# bbf-supply.net
KiCad netlist of a schematic drawn in EAGLE
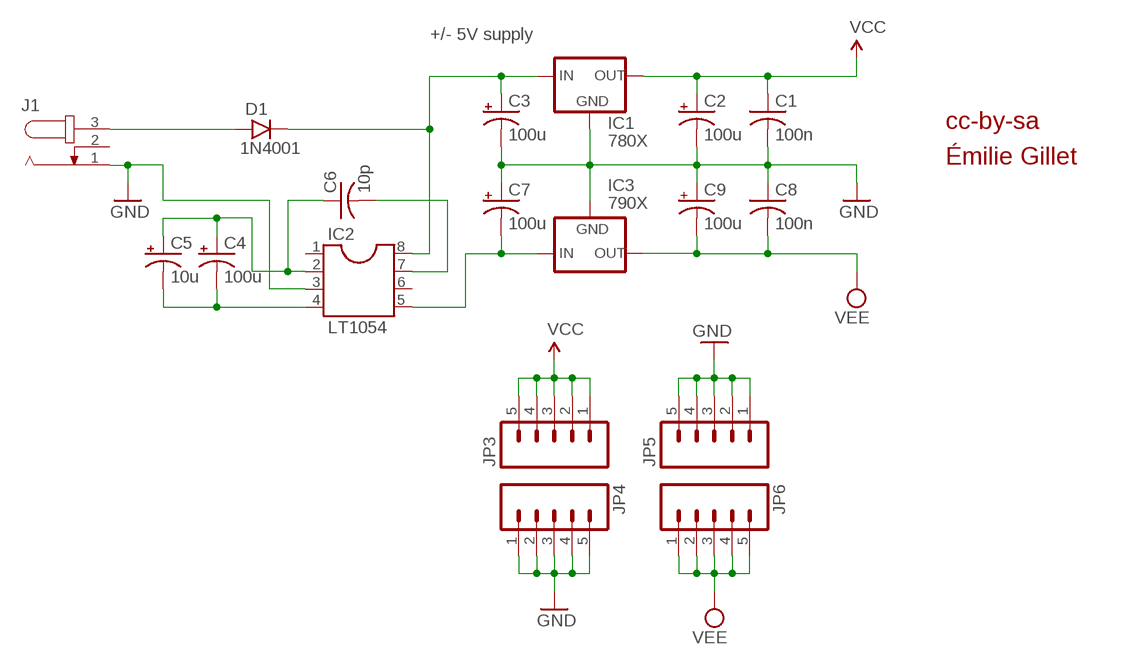
[diagram p0: schematic, sheet 1]

(export (version "E")
  (design (tool "Eeschema 10.0.6"))
  (components
    (comp (ref "C1")
      (value "100n")
      (footprint "eagle-import:C025-025X050")
      (libsource (lib "eagle-import") (part "C-US025-025X050"))
    )
    (comp (ref "C2")
      (value "100u")
      (footprint "eagle-import:E2,5-7")
      (libsource (lib "eagle-import") (part "CPOL-USE2.5-7"))
    )
    (comp (ref "C3")
      (value "100u")
      (footprint "eagle-import:E2,5-7")
      (libsource (lib "eagle-import") (part "CPOL-USE2.5-7"))
    )
    (comp (ref "C4")
      (value "100u")
      (footprint "eagle-import:E2,5-6")
      (libsource (lib "eagle-import") (part "CPOL-USE2.5-6"))
    )
    (comp (ref "C5")
      (value "10u")
      (footprint "eagle-import:E2,5-5")
      (libsource (lib "eagle-import") (part "CPOL-USE2.5-5"))
    )
    (comp (ref "C6")
      (value "10p")
      (footprint "eagle-import:C025-025X050")
      (libsource (lib "eagle-import") (part "C-US025-025X050"))
    )
    (comp (ref "C7")
      (value "100u")
      (footprint "eagle-import:E2,5-7")
      (libsource (lib "eagle-import") (part "CPOL-USE2.5-7"))
    )
    (comp (ref "C8")
      (value "100n")
      (footprint "eagle-import:C025-025X050")
      (libsource (lib "eagle-import") (part "C-US025-025X050"))
    )
    (comp (ref "C9")
      (value "100u")
      (footprint "eagle-import:E2,5-7")
      (libsource (lib "eagle-import") (part "CPOL-USE2.5-7"))
    )
    (comp (ref "D1")
      (value "1N4001")
      (footprint "eagle-import:DO41-3")
      (libsource (lib "eagle-import") (part "1N400X.3"))
    )
    (comp (ref "IC1")
      (value "780X")
      (footprint "eagle-import:78XXS")
      (libsource (lib "eagle-import") (part "78XXS"))
    )
    (comp (ref "IC2")
      (value "LT1054")
      (footprint "eagle-import:DIL08")
      (libsource (lib "eagle-import") (part "DIL8"))
    )
    (comp (ref "IC3")
      (value "790X")
      (footprint "eagle-import:79XXS")
      (libsource (lib "eagle-import") (part "79XXS"))
    )
    (comp (ref "J1")
      (value "JACK-PLUG2")
      (footprint "eagle-import:SPC4078_BIG_HOLES")
      (libsource (lib "eagle-import") (part "JACK-PLUG2"))
    )
    (comp (ref "JP3")
      (value "M05PTH")
      (footprint "eagle-import:1X05")
      (libsource (lib "eagle-import") (part "M05PTH"))
    )
    (comp (ref "JP4")
      (value "M05PTH")
      (footprint "eagle-import:1X05")
      (libsource (lib "eagle-import") (part "M05PTH"))
    )
    (comp (ref "JP5")
      (value "M05PTH")
      (footprint "eagle-import:1X05")
      (libsource (lib "eagle-import") (part "M05PTH"))
    )
    (comp (ref "JP6")
      (value "M05PTH")
      (footprint "eagle-import:1X05")
      (libsource (lib "eagle-import") (part "M05PTH"))
    )
  )
  (nets
    (net (code "1") (name "GND") (class "Default")
      (node (ref "C1") (pin "2") (pinfunction "2_2") (pintype "passive"))
      (node (ref "C2") (pin "-") (pinfunction "-_-") (pintype "passive"))
      (node (ref "C3") (pin "-") (pinfunction "-_-") (pintype "passive"))
      (node (ref "C7") (pin "+") (pinfunction "+_+") (pintype "passive"))
      (node (ref "C8") (pin "1") (pinfunction "1_1") (pintype "passive"))
      (node (ref "C9") (pin "+") (pinfunction "+_+") (pintype "passive"))
      (node (ref "IC1") (pin "GND") (pinfunction "GND_GND") (pintype "input"))
      (node (ref "IC2") (pin "3") (pinfunction "3_3") (pintype "passive"))
      (node (ref "IC3") (pin "GND") (pinfunction "GND_GND") (pintype "input"))
      (node (ref "J1") (pin "1") (pinfunction "1_1") (pintype "passive"))
      (node (ref "JP4") (pin "1") (pinfunction "1_1") (pintype "passive"))
      (node (ref "JP4") (pin "2") (pinfunction "2_2") (pintype "passive"))
      (node (ref "JP4") (pin "3") (pinfunction "3_3") (pintype "passive"))
      (node (ref "JP4") (pin "4") (pinfunction "4_4") (pintype "passive"))
      (node (ref "JP4") (pin "5") (pinfunction "5_5") (pintype "passive"))
      (node (ref "JP5") (pin "1") (pinfunction "1_1") (pintype "passive"))
      (node (ref "JP5") (pin "2") (pinfunction "2_2") (pintype "passive"))
      (node (ref "JP5") (pin "3") (pinfunction "3_3") (pintype "passive"))
      (node (ref "JP5") (pin "4") (pinfunction "4_4") (pintype "passive"))
      (node (ref "JP5") (pin "5") (pinfunction "5_5") (pintype "passive"))
    )
    (net (code "2") (name "Net-(C3-Pad+)") (class "Default")
      (node (ref "C3") (pin "+") (pinfunction "+_+") (pintype "passive"))
      (node (ref "D1") (pin "C") (pinfunction "C_C") (pintype "passive"))
      (node (ref "IC1") (pin "IN") (pinfunction "IN_IN") (pintype "input"))
      (node (ref "IC2") (pin "8") (pinfunction "8_8") (pintype "passive"))
    )
    (net (code "3") (name "Net-(C4-Pad+)") (class "Default")
      (node (ref "C4") (pin "+") (pinfunction "+_+") (pintype "passive"))
      (node (ref "C5") (pin "+") (pinfunction "+_+") (pintype "passive"))
      (node (ref "C6") (pin "1") (pinfunction "1_1") (pintype "passive"))
      (node (ref "IC2") (pin "2") (pinfunction "2_2") (pintype "passive"))
    )
    (net (code "4") (name "Net-(C4-Pad-)") (class "Default")
      (node (ref "C4") (pin "-") (pinfunction "-_-") (pintype "passive"))
      (node (ref "C5") (pin "-") (pinfunction "-_-") (pintype "passive"))
      (node (ref "IC2") (pin "4") (pinfunction "4_4") (pintype "passive"))
    )
    (net (code "5") (name "Net-(C6-Pad2)") (class "Default")
      (node (ref "C6") (pin "2") (pinfunction "2_2") (pintype "passive"))
      (node (ref "IC2") (pin "7") (pinfunction "7_7") (pintype "passive"))
    )
    (net (code "6") (name "Net-(C7-Pad-)") (class "Default")
      (node (ref "C7") (pin "-") (pinfunction "-_-") (pintype "passive"))
      (node (ref "IC2") (pin "5") (pinfunction "5_5") (pintype "passive"))
      (node (ref "IC3") (pin "IN") (pinfunction "IN_IN") (pintype "input"))
    )
    (net (code "7") (name "Net-(D1-PadA)") (class "Default")
      (node (ref "D1") (pin "A") (pinfunction "A_A") (pintype "passive"))
      (node (ref "J1") (pin "3") (pinfunction "3_3") (pintype "passive"))
    )
    (net (code "8") (name "VCC") (class "Default")
      (node (ref "C1") (pin "1") (pinfunction "1_1") (pintype "passive"))
      (node (ref "C2") (pin "+") (pinfunction "+_+") (pintype "passive"))
      (node (ref "IC1") (pin "OUT") (pinfunction "OUT_OUT") (pintype "passive"))
      (node (ref "JP3") (pin "1") (pinfunction "1_1") (pintype "passive"))
      (node (ref "JP3") (pin "2") (pinfunction "2_2") (pintype "passive"))
      (node (ref "JP3") (pin "3") (pinfunction "3_3") (pintype "passive"))
      (node (ref "JP3") (pin "4") (pinfunction "4_4") (pintype "passive"))
      (node (ref "JP3") (pin "5") (pinfunction "5_5") (pintype "passive"))
    )
    (net (code "9") (name "VEE") (class "Default")
      (node (ref "C8") (pin "2") (pinfunction "2_2") (pintype "passive"))
      (node (ref "C9") (pin "-") (pinfunction "-_-") (pintype "passive"))
      (node (ref "IC3") (pin "OUT") (pinfunction "OUT_OUT") (pintype "passive"))
      (node (ref "JP6") (pin "1") (pinfunction "1_1") (pintype "passive"))
      (node (ref "JP6") (pin "2") (pinfunction "2_2") (pintype "passive"))
      (node (ref "JP6") (pin "3") (pinfunction "3_3") (pintype "passive"))
      (node (ref "JP6") (pin "4") (pinfunction "4_4") (pintype "passive"))
      (node (ref "JP6") (pin "5") (pinfunction "5_5") (pintype "passive"))
    )
    (net (code "10") (name "unconnected-(IC2-Pad1)") (class "Default")
      (node (ref "IC2") (pin "1") (pinfunction "1_1") (pintype "passive"))
    )
    (net (code "11") (name "unconnected-(IC2-Pad6)") (class "Default")
      (node (ref "IC2") (pin "6") (pinfunction "6_6") (pintype "passive"))
    )
    (net (code "12") (name "unconnected-(J1-Pad2)") (class "Default")
      (node (ref "J1") (pin "2") (pinfunction "2_2") (pintype "passive"))
    )
  )
)
